# main.net
KiCad netlist of a schematic drawn in Altium Designer
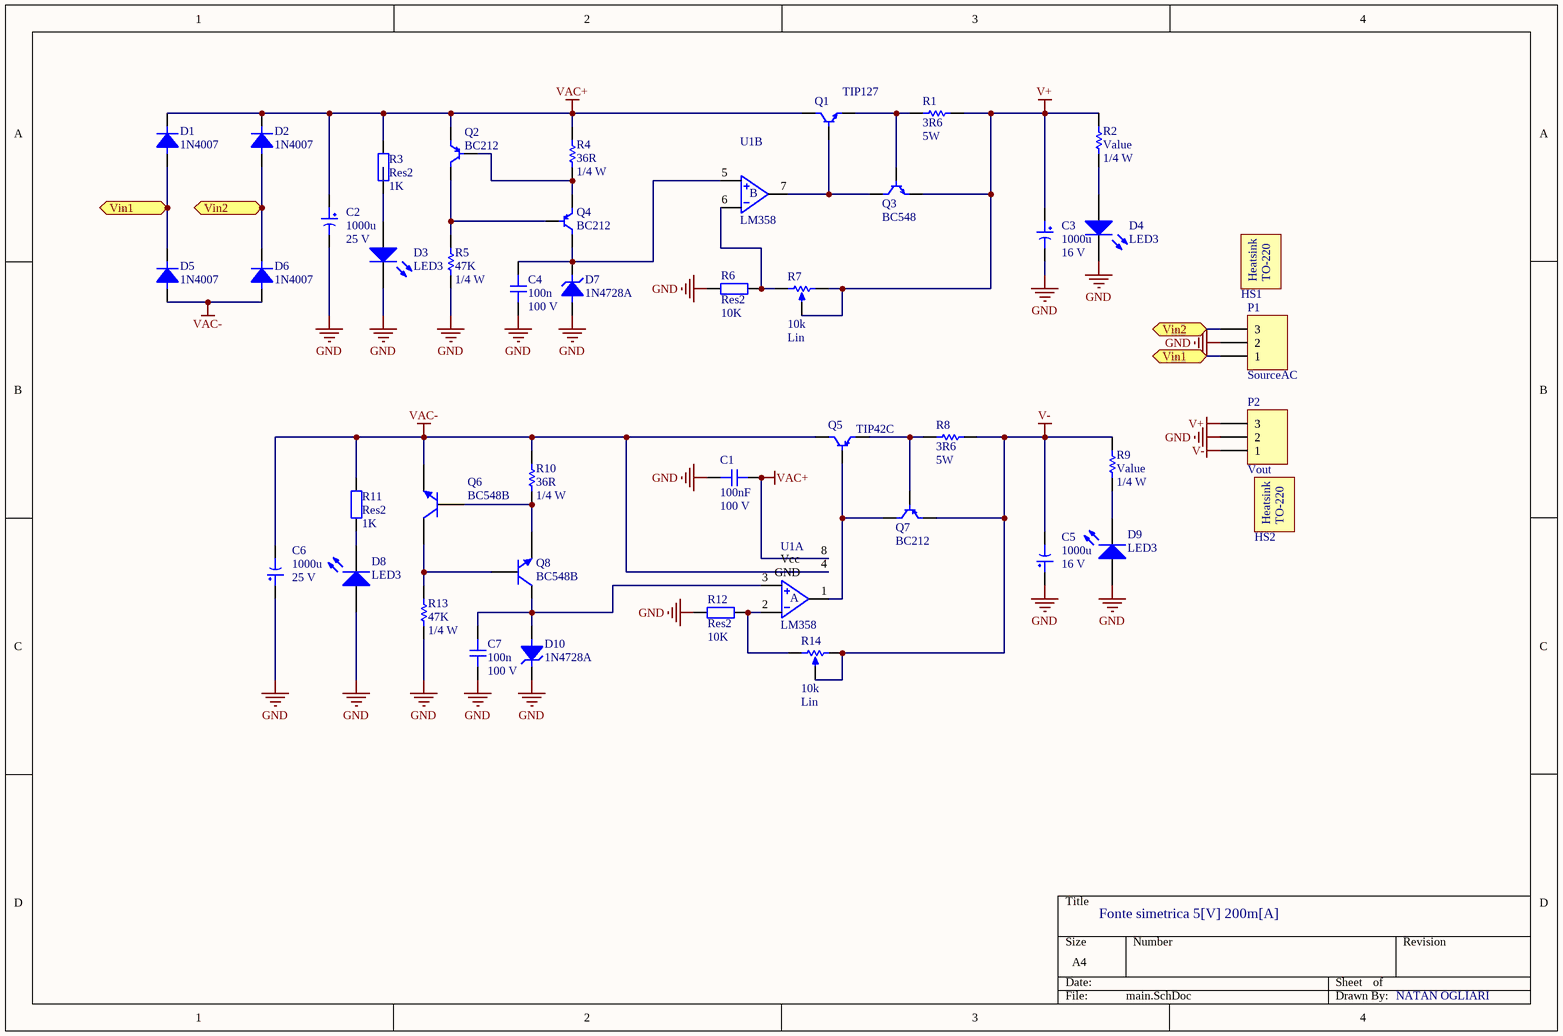
[diagram p0: main.SchDoc]

(export (version "E")
  (design (tool "Eeschema 10.0.6"))
  (components
    (comp (ref "C1")
      (value "100nF")
      (footprint "0805C")
      (description "Capacitor")
      (fields (field (name "VOLTAGE") "100 V") (field (name "PUBLISHER") "Altium Limited"))
      (libsource (lib "GPDSE") (part "Capacitor"))
    )
    (comp (ref "C2")
      (value "1000u")
      (footprint "CP-RAD-16.0mm-15.0mm-7.5mm")
      (description "Electrolytic Capacitor")
      (fields (field (name "VOLTAGE") "25 V"))
      (libsource (lib "GPDSE") (part "Capacitor-Electrolytic"))
    )
    (comp (ref "C3")
      (value "1000u")
      (footprint "CP-RAD-16.0mm-31.5mm-7.5mm")
      (description "Electrolytic Capacitor")
      (fields (field (name "VOLTAGE") "16 V"))
      (libsource (lib "GPDSE") (part "Capacitor-Electrolytic"))
    )
    (comp (ref "C4")
      (value "100n")
      (footprint "C100-200-100")
      (description "Capacitor")
      (fields (field (name "VOLTAGE") "100 V") (field (name "PUBLISHER") "Altium Limited"))
      (libsource (lib "GPDSE") (part "Capacitor"))
    )
    (comp (ref "C5")
      (value "1000u")
      (footprint "CP-RAD-16.0mm-15.0mm-7.5mm")
      (description "Electrolytic Capacitor")
      (fields (field (name "VOLTAGE") "16 V"))
      (libsource (lib "GPDSE") (part "Capacitor-Electrolytic"))
    )
    (comp (ref "C6")
      (value "1000u")
      (footprint "CP-RAD-16.0mm-15.0mm-7.5mm")
      (description "Electrolytic Capacitor")
      (fields (field (name "VOLTAGE") "25 V"))
      (libsource (lib "GPDSE") (part "Capacitor-Electrolytic"))
    )
    (comp (ref "C7")
      (value "100n")
      (footprint "C100-200-100")
      (description "Capacitor")
      (fields (field (name "VOLTAGE") "100 V") (field (name "PUBLISHER") "Altium Limited"))
      (libsource (lib "GPDSE") (part "Capacitor"))
    )
    (comp (ref "D1")
      (value "1N4007")
      (footprint "DO-41-Plastic")
      (description "General Purpose Rectifier")
      (libsource (lib "GPDSE") (part "1N4007"))
    )
    (comp (ref "D2")
      (value "1N4007")
      (footprint "DO-41-Plastic")
      (description "General Purpose Rectifier")
      (libsource (lib "GPDSE") (part "1N4007"))
    )
    (comp (ref "D3")
      (value "LED3")
      (footprint "LED 5mm")
      (description "Typical BLUE SiC LED")
      (fields (field (name "PUBLISHER") "Altium Limited"))
      (libsource (lib "Miscellaneous Devices") (part "LED3"))
    )
    (comp (ref "D4")
      (value "LED3")
      (footprint "LED 5mm")
      (description "Typical BLUE SiC LED")
      (fields (field (name "PUBLISHER") "Altium Limited"))
      (libsource (lib "Miscellaneous Devices") (part "LED3"))
    )
    (comp (ref "D5")
      (value "1N4007")
      (footprint "DO-41-Plastic")
      (description "General Purpose Rectifier")
      (libsource (lib "GPDSE") (part "1N4007"))
    )
    (comp (ref "D6")
      (value "1N4007")
      (footprint "DO-41-Plastic")
      (description "General Purpose Rectifier")
      (libsource (lib "GPDSE") (part "1N4007"))
    )
    (comp (ref "D7")
      (value "1N4728A")
      (footprint "DO-41-Glass")
      (description "Zener Diode")
      (libsource (lib "GPDSE") (part "1N4728A"))
    )
    (comp (ref "D8")
      (value "LED3")
      (footprint "LED 5mm")
      (description "Typical BLUE SiC LED")
      (fields (field (name "PUBLISHER") "Altium Limited"))
      (libsource (lib "Miscellaneous Devices") (part "LED3"))
    )
    (comp (ref "D9")
      (value "LED3")
      (footprint "LED 5mm")
      (description "Typical BLUE SiC LED")
      (fields (field (name "PUBLISHER") "Altium Limited"))
      (libsource (lib "Miscellaneous Devices") (part "LED3"))
    )
    (comp (ref "D10")
      (value "1N4728A")
      (footprint "DO-41-Glass")
      (description "Zener Diode")
      (libsource (lib "GPDSE") (part "1N4728A"))
    )
    (comp (ref "HS1")
      (value "HS-TO-220")
      (footprint "HS-TO-220-180847")
      (description "Heatsink TO-220")
      (libsource (lib "GPDSE") (part "HS-TO-220"))
    )
    (comp (ref "HS2")
      (value "HS-TO-220")
      (footprint "HS-TO-220-180847")
      (description "Heatsink TO-220")
      (libsource (lib "GPDSE") (part "HS-TO-220"))
    )
    (comp (ref "P1")
      (value "SourceAC")
      (footprint "KRE_3")
      (description "Terminal Block 1x3")
      (libsource (lib "GPDSE") (part "KRE_3"))
    )
    (comp (ref "P2")
      (value "Vout")
      (footprint "KRE_3")
      (description "Terminal Block 1x3")
      (libsource (lib "GPDSE") (part "KRE_3"))
    )
    (comp (ref "Q1")
      (value "TIP127")
      (footprint "TO-220/BCE")
      (description "NPN Epitaxial Silicon Transistor")
      (fields (field (name "COMPLEMENTARY PART") "BC328"))
      (libsource (lib "GPDSE") (part "BC338"))
    )
    (comp (ref "Q2")
      (value "BC212")
      (footprint "TO-92/CBE")
      (description "PNP Epitaxial Silicon Transistor")
      (fields (field (name "COMPLEMENTARY PART") "BC546"))
      (libsource (lib "GPDSE") (part "BC556"))
    )
    (comp (ref "Q3")
      (value "BC548")
      (footprint "TO-92/CBE")
      (description "NPN Epitaxial Silicon Transistor")
      (fields (field (name "COMPLEMENTARY PART") "BC328"))
      (libsource (lib "GPDSE") (part "BC338"))
    )
    (comp (ref "Q4")
      (value "BC212")
      (footprint "TO-92/CBE")
      (description "PNP Epitaxial Silicon Transistor")
      (fields (field (name "COMPLEMENTARY PART") "BC546"))
      (libsource (lib "GPDSE") (part "BC556"))
    )
    (comp (ref "Q5")
      (value "TIP42C")
      (footprint "TO-220AB")
      (description "PNP Epitaxial Silicon Transistor")
      (fields (field (name "COMPLEMENTARY PART") "BC338"))
      (libsource (lib "GPDSE") (part "BC328"))
    )
    (comp (ref "Q6")
      (value "BC548B")
      (footprint "29-04")
      (description "Amplifier Transistor NPN Silicon")
      (fields (field (name "PUBLISHER") "Altium Limited"))
      (libsource (lib "Motorola Discrete BJT") (part "BC548B"))
    )
    (comp (ref "Q7")
      (value "BC212")
      (footprint "TO-92/CBE")
      (description "PNP Epitaxial Silicon Transistor")
      (fields (field (name "COMPLEMENTARY PART") "BC338"))
      (libsource (lib "GPDSE") (part "BC328"))
    )
    (comp (ref "Q8")
      (value "BC548B")
      (footprint "29-04")
      (description "Amplifier Transistor NPN Silicon")
      (fields (field (name "PUBLISHER") "Altium Limited"))
      (libsource (lib "Motorola Discrete BJT") (part "BC548B"))
    )
    (comp (ref "R1")
      (value "3R6")
      (footprint "Res Axial 1W")
      (description "Resistor")
      (fields
        (field (name "TOLERANCE") "5%")
        (field (name "POWER") "5W")
        (field (name "PUBLISHER") "Altium Limited")
      )
      (libsource (lib "GPDSE") (part "Resistor"))
    )
    (comp (ref "R2")
      (value "Value")
      (footprint "R400-2.0mm")
      (description "Resistor")
      (fields
        (field (name "TOLERANCE") "5%")
        (field (name "POWER") "1/4 W")
        (field (name "PUBLISHER") "Altium Limited")
      )
      (libsource (lib "GPDSE") (part "Resistor"))
    )
    (comp (ref "R3")
      (value "Res2")
      (footprint "AXIAL-0.4")
      (description "Resistor")
      (fields (field (name "ALTIUM_VALUE") "1K") (field (name "PUBLISHER") "Altium Limited"))
      (libsource (lib "Miscellaneous Devices") (part "Res2"))
    )
    (comp (ref "R4")
      (value "36R")
      (footprint "R400-2.0mm")
      (description "Resistor")
      (fields
        (field (name "TOLERANCE") "5%")
        (field (name "POWER") "1/4 W")
        (field (name "PUBLISHER") "Altium Limited")
      )
      (libsource (lib "GPDSE") (part "Resistor"))
    )
    (comp (ref "R5")
      (value "47K")
      (footprint "R400-2.0mm")
      (description "Resistor")
      (fields
        (field (name "TOLERANCE") "5%")
        (field (name "POWER") "1/4 W")
        (field (name "PUBLISHER") "Altium Limited")
      )
      (libsource (lib "GPDSE") (part "Resistor"))
    )
    (comp (ref "R6")
      (value "Res2")
      (footprint "AXIAL-0.4")
      (description "Resistor")
      (fields (field (name "ALTIUM_VALUE") "10K") (field (name "PUBLISHER") "Altium Limited"))
      (libsource (lib "") (part "Res2_1"))
    )
    (comp (ref "R7")
      (value "10k")
      (footprint "Trimpot-3266Y")
      (description "Potentiometer")
      (fields (field (name "TYPE") "Lin"))
      (libsource (lib "GPDSE") (part "Potentiometer"))
    )
    (comp (ref "R8")
      (value "3R6")
      (footprint "Res Axial 1W")
      (description "Resistor")
      (fields
        (field (name "TOLERANCE") "5%")
        (field (name "POWER") "5W")
        (field (name "PUBLISHER") "Altium Limited")
      )
      (libsource (lib "GPDSE") (part "Resistor"))
    )
    (comp (ref "R9")
      (value "Value")
      (footprint "R400-2.0mm")
      (description "Resistor")
      (fields
        (field (name "TOLERANCE") "5%")
        (field (name "POWER") "1/4 W")
        (field (name "PUBLISHER") "Altium Limited")
      )
      (libsource (lib "GPDSE") (part "Resistor"))
    )
    (comp (ref "R10")
      (value "36R")
      (footprint "R400-2.0mm")
      (description "Resistor")
      (fields
        (field (name "TOLERANCE") "5%")
        (field (name "POWER") "1/4 W")
        (field (name "PUBLISHER") "Altium Limited")
      )
      (libsource (lib "GPDSE") (part "Resistor"))
    )
    (comp (ref "R11")
      (value "Res2")
      (footprint "AXIAL-0.4")
      (description "Resistor")
      (fields (field (name "ALTIUM_VALUE") "1K") (field (name "PUBLISHER") "Altium Limited"))
      (libsource (lib "Miscellaneous Devices") (part "Res2"))
    )
    (comp (ref "R12")
      (value "Res2")
      (footprint "AXIAL-0.4")
      (description "Resistor")
      (fields (field (name "ALTIUM_VALUE") "10K") (field (name "PUBLISHER") "Altium Limited"))
      (libsource (lib "") (part "Res2_1"))
    )
    (comp (ref "R13")
      (value "47K")
      (footprint "R400-2.0mm")
      (description "Resistor")
      (fields
        (field (name "TOLERANCE") "5%")
        (field (name "POWER") "1/4 W")
        (field (name "PUBLISHER") "Altium Limited")
      )
      (libsource (lib "GPDSE") (part "Resistor"))
    )
    (comp (ref "R14")
      (value "10k")
      (footprint "Trimpot-3266Y")
      (description "Potentiometer")
      (fields (field (name "TYPE") "Lin"))
      (libsource (lib "GPDSE") (part "Potentiometer"))
    )
    (comp (ref "U1")
      (value "LM358")
      (footprint "DIP08-300(100)")
      (description "Dual Operational Amplifier")
      (libsource (lib "GPDSE") (part "LM358"))
    )
  )
  (nets
    (net (code "1") (name "/Vin1") (class "Default")
      (node (ref "D1") (pin "A") (pinfunction "A_A") (pintype "passive"))
      (node (ref "D5") (pin "K") (pinfunction "K_K") (pintype "passive"))
      (node (ref "P1") (pin "1") (pinfunction "1_1") (pintype "passive"))
    )
    (net (code "2") (name "/Vin2") (class "Default")
      (node (ref "D2") (pin "A") (pinfunction "A_A") (pintype "passive"))
      (node (ref "D6") (pin "K") (pinfunction "K_K") (pintype "passive"))
      (node (ref "P1") (pin "3") (pinfunction "3_3") (pintype "passive"))
    )
    (net (code "3") (name "GND") (class "Default")
      (node (ref "C1") (pin "2") (pinfunction "2_2") (pintype "passive"))
      (node (ref "C2") (pin "2") (pinfunction "2_2") (pintype "passive"))
      (node (ref "C3") (pin "2") (pinfunction "2_2") (pintype "passive"))
      (node (ref "C4") (pin "1") (pinfunction "1_1") (pintype "passive"))
      (node (ref "C5") (pin "1") (pinfunction "1_1") (pintype "passive"))
      (node (ref "C6") (pin "1") (pinfunction "1_1") (pintype "passive"))
      (node (ref "C7") (pin "1") (pinfunction "1_1") (pintype "passive"))
      (node (ref "D10") (pin "K") (pinfunction "K_K") (pintype "passive"))
      (node (ref "D3") (pin "2") (pinfunction "K_2") (pintype "passive"))
      (node (ref "D4") (pin "2") (pinfunction "K_2") (pintype "passive"))
      (node (ref "D7") (pin "A") (pinfunction "A_A") (pintype "passive"))
      (node (ref "D8") (pin "1") (pinfunction "A_1") (pintype "passive"))
      (node (ref "D9") (pin "1") (pinfunction "A_1") (pintype "passive"))
      (node (ref "P1") (pin "2") (pinfunction "2_2") (pintype "passive"))
      (node (ref "P2") (pin "2") (pinfunction "2_2") (pintype "passive"))
      (node (ref "R12") (pin "1") (pinfunction "1_1") (pintype "passive"))
      (node (ref "R13") (pin "1") (pinfunction "1_1") (pintype "passive"))
      (node (ref "R5") (pin "1") (pinfunction "1_1") (pintype "passive"))
      (node (ref "R6") (pin "1") (pinfunction "1_1") (pintype "passive"))
    )
    (net (code "4") (name "Net-(D3-A)") (class "Default")
      (node (ref "D3") (pin "1") (pinfunction "A_1") (pintype "passive"))
      (node (ref "R3") (pin "1") (pinfunction "1_1") (pintype "passive"))
    )
    (net (code "5") (name "Net-(D4-A)") (class "Default")
      (node (ref "D4") (pin "1") (pinfunction "A_1") (pintype "passive"))
      (node (ref "R2") (pin "1") (pinfunction "1_1") (pintype "passive"))
    )
    (net (code "6") (name "Net-(D8-K)") (class "Default")
      (node (ref "D8") (pin "2") (pinfunction "K_2") (pintype "passive"))
      (node (ref "R11") (pin "1") (pinfunction "1_1") (pintype "passive"))
    )
    (net (code "7") (name "Net-(D9-K)") (class "Default")
      (node (ref "D9") (pin "2") (pinfunction "K_2") (pintype "passive"))
      (node (ref "R9") (pin "1") (pinfunction "1_1") (pintype "passive"))
    )
    (net (code "8") (name "Net-(Q1-PadE)") (class "Default")
      (node (ref "Q1") (pin "E") (pinfunction "E_E") (pintype "passive"))
      (node (ref "Q3") (pin "B") (pinfunction "B_B") (pintype "passive"))
      (node (ref "R1") (pin "1") (pinfunction "1_1") (pintype "passive"))
    )
    (net (code "9") (name "Net-(Q2-PadB)") (class "Default")
      (node (ref "Q2") (pin "B") (pinfunction "B_B") (pintype "passive"))
      (node (ref "Q4") (pin "E") (pinfunction "E_E") (pintype "passive"))
      (node (ref "R4") (pin "1") (pinfunction "1_1") (pintype "passive"))
    )
    (net (code "10") (name "Net-(Q2-PadC)") (class "Default")
      (node (ref "Q2") (pin "C") (pinfunction "C_C") (pintype "passive"))
      (node (ref "Q4") (pin "B") (pinfunction "B_B") (pintype "passive"))
      (node (ref "R5") (pin "2") (pinfunction "2_2") (pintype "passive"))
    )
    (net (code "11") (name "Net-(Q5-PadE)") (class "Default")
      (node (ref "Q5") (pin "E") (pinfunction "E_E") (pintype "passive"))
      (node (ref "Q7") (pin "B") (pinfunction "B_B") (pintype "passive"))
      (node (ref "R8") (pin "1") (pinfunction "1_1") (pintype "passive"))
    )
    (net (code "12") (name "Net-(Q6-B)") (class "Default")
      (node (ref "Q6") (pin "2") (pinfunction "B_2") (pintype "passive"))
      (node (ref "Q8") (pin "3") (pinfunction "E_3") (pintype "passive"))
      (node (ref "R10") (pin "1") (pinfunction "1_1") (pintype "passive"))
    )
    (net (code "13") (name "Net-(Q6-C)") (class "Default")
      (node (ref "Q6") (pin "1") (pinfunction "C_1") (pintype "passive"))
      (node (ref "Q8") (pin "2") (pinfunction "B_2") (pintype "passive"))
      (node (ref "R13") (pin "2") (pinfunction "2_2") (pintype "passive"))
    )
    (net (code "14") (name "Net-(Q8-C)") (class "Default")
      (node (ref "C7") (pin "2") (pinfunction "2_2") (pintype "passive"))
      (node (ref "D10") (pin "A") (pinfunction "A_A") (pintype "passive"))
      (node (ref "Q8") (pin "1") (pinfunction "C_1") (pintype "passive"))
      (node (ref "U1") (pin "3") (pinfunction "IN1+_3") (pintype "passive"))
    )
    (net (code "15") (name "Net-(R7-TOP)") (class "Default")
      (node (ref "R6") (pin "2") (pinfunction "2_2") (pintype "passive"))
      (node (ref "R7") (pin "1") (pinfunction "TOP_1") (pintype "passive"))
      (node (ref "U1") (pin "6") (pinfunction "IN2-_6") (pintype "passive"))
    )
    (net (code "16") (name "Net-(R14-TOP)") (class "Default")
      (node (ref "R12") (pin "2") (pinfunction "2_2") (pintype "passive"))
      (node (ref "R14") (pin "1") (pinfunction "TOP_1") (pintype "passive"))
      (node (ref "U1") (pin "2") (pinfunction "IN1-_2") (pintype "passive"))
    )
    (net (code "17") (name "Net-(U1A-O1)") (class "Default")
      (node (ref "Q5") (pin "B") (pinfunction "B_B") (pintype "passive"))
      (node (ref "Q7") (pin "C") (pinfunction "C_C") (pintype "passive"))
      (node (ref "U1") (pin "1") (pinfunction "O1_1") (pintype "passive"))
    )
    (net (code "18") (name "Net-(U1B-IN2+)") (class "Default")
      (node (ref "C4") (pin "2") (pinfunction "2_2") (pintype "passive"))
      (node (ref "D7") (pin "K") (pinfunction "K_K") (pintype "passive"))
      (node (ref "Q4") (pin "C") (pinfunction "C_C") (pintype "passive"))
      (node (ref "U1") (pin "5") (pinfunction "IN2+_5") (pintype "passive"))
    )
    (net (code "19") (name "Net-(U1B-O2)") (class "Default")
      (node (ref "Q1") (pin "B") (pinfunction "B_B") (pintype "passive"))
      (node (ref "Q3") (pin "C") (pinfunction "C_C") (pintype "passive"))
      (node (ref "U1") (pin "7") (pinfunction "O2_7") (pintype "passive"))
    )
    (net (code "20") (name "V+") (class "Default")
      (node (ref "C3") (pin "1") (pinfunction "1_1") (pintype "passive"))
      (node (ref "P2") (pin "3") (pinfunction "3_3") (pintype "passive"))
      (node (ref "Q3") (pin "E") (pinfunction "E_E") (pintype "passive"))
      (node (ref "R1") (pin "2") (pinfunction "2_2") (pintype "passive"))
      (node (ref "R2") (pin "2") (pinfunction "2_2") (pintype "passive"))
      (node (ref "R7") (pin "2") (pinfunction "TAP_2") (pintype "passive"))
      (node (ref "R7") (pin "3") (pinfunction "BOT_3") (pintype "passive"))
    )
    (net (code "21") (name "V-") (class "Default")
      (node (ref "C5") (pin "2") (pinfunction "2_2") (pintype "passive"))
      (node (ref "P2") (pin "1") (pinfunction "1_1") (pintype "passive"))
      (node (ref "Q7") (pin "E") (pinfunction "E_E") (pintype "passive"))
      (node (ref "R14") (pin "2") (pinfunction "TAP_2") (pintype "passive"))
      (node (ref "R14") (pin "3") (pinfunction "BOT_3") (pintype "passive"))
      (node (ref "R8") (pin "2") (pinfunction "2_2") (pintype "passive"))
      (node (ref "R9") (pin "2") (pinfunction "2_2") (pintype "passive"))
    )
    (net (code "22") (name "VAC+") (class "Default")
      (node (ref "C1") (pin "1") (pinfunction "1_1") (pintype "passive"))
      (node (ref "C2") (pin "1") (pinfunction "1_1") (pintype "passive"))
      (node (ref "D1") (pin "K") (pinfunction "K_K") (pintype "passive"))
      (node (ref "D2") (pin "K") (pinfunction "K_K") (pintype "passive"))
      (node (ref "Q1") (pin "C") (pinfunction "C_C") (pintype "passive"))
      (node (ref "Q2") (pin "E") (pinfunction "E_E") (pintype "passive"))
      (node (ref "R3") (pin "2") (pinfunction "2_2") (pintype "passive"))
      (node (ref "R4") (pin "2") (pinfunction "2_2") (pintype "passive"))
      (node (ref "U1") (pin "8") (pinfunction "Vcc_8") (pintype "power_in"))
    )
    (net (code "23") (name "VAC-") (class "Default")
      (node (ref "C6") (pin "2") (pinfunction "2_2") (pintype "passive"))
      (node (ref "D5") (pin "A") (pinfunction "A_A") (pintype "passive"))
      (node (ref "D6") (pin "A") (pinfunction "A_A") (pintype "passive"))
      (node (ref "Q5") (pin "C") (pinfunction "C_C") (pintype "passive"))
      (node (ref "Q6") (pin "3") (pinfunction "E_3") (pintype "passive"))
      (node (ref "R10") (pin "2") (pinfunction "2_2") (pintype "passive"))
      (node (ref "R11") (pin "2") (pinfunction "2_2") (pintype "passive"))
      (node (ref "U1") (pin "4") (pinfunction "GND_4") (pintype "power_in"))
    )
  )
)
